# SENSOR.net
KiCad netlist of a schematic drawn in Altium Designer
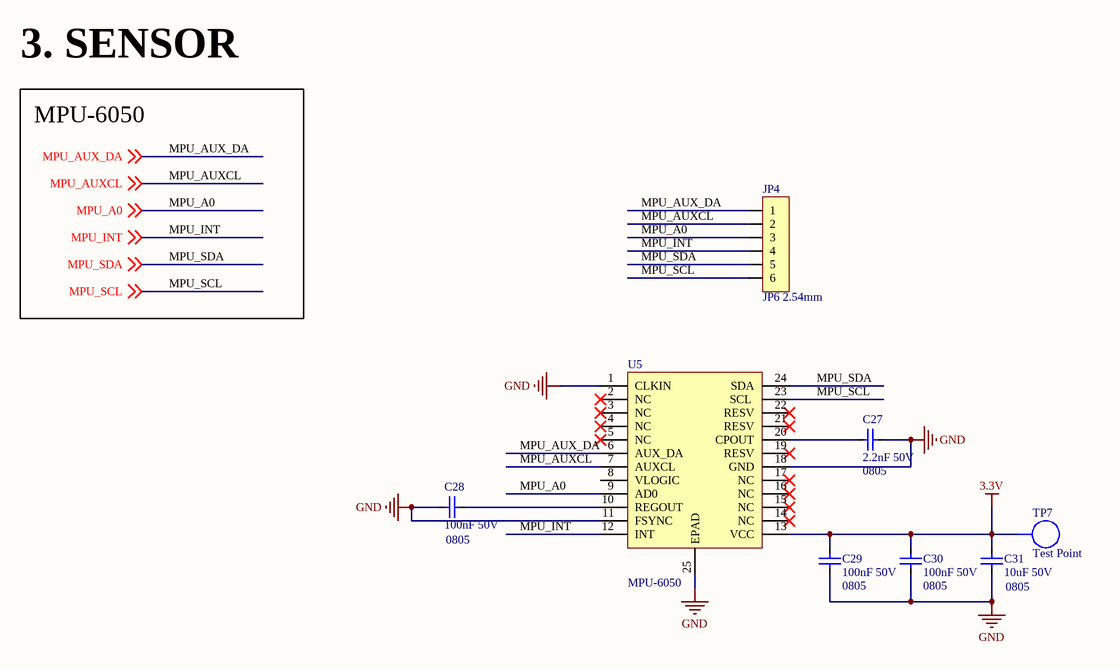
[diagram p0: SENSOR.SchDoc]

(export (version "E")
  (design (tool "Eeschema 10.0.6"))
  (components
    (comp (ref "C27")
      (value "2.2nF 50V")
      (footprint "CAP_SMD_0805_NEW")
      (description "2200 pF ±1% 50V Ceramic Capacitor C0G, NP0 0805 (2012 Metric)")
      (fields
        (field (name "MANUFACTURER") "YAGEO")
        (field (name "MANUFACTURE PART NUMBER") "CC0805FKNPO9BN222")
        (field (name "SIZE") "0805")
      )
      (libsource (lib "Capacitors") (part "C0805_MLCC_2.2nF_50V"))
    )
    (comp (ref "C28")
      (value "100nF 50V")
      (footprint "CAP_SMD_0805_NEW")
      (description "0.1 µF ±10% 50V Ceramic Capacitor X7R 0805 (2012 Metric)")
      (fields
        (field (name "MANUFACTURER") "YAGEO")
        (field (name "MANUFACTURE PART NUMBER") "CC0805KRX7R9BB104")
        (field (name "SIZE") "0805")
      )
      (libsource (lib "Capacitors") (part "C0805_MLCC_100nF_50V"))
    )
    (comp (ref "C29")
      (value "100nF 50V")
      (footprint "CAP_SMD_0805_NEW")
      (description "0.1 µF ±10% 50V Ceramic Capacitor X7R 0805 (2012 Metric)")
      (fields
        (field (name "MANUFACTURER") "YAGEO")
        (field (name "MANUFACTURE PART NUMBER") "CC0805KRX7R9BB104")
        (field (name "SIZE") "0805")
      )
      (libsource (lib "Capacitors") (part "C0805_MLCC_100nF_50V"))
    )
    (comp (ref "C30")
      (value "100nF 50V")
      (footprint "CAP_SMD_0805_NEW")
      (description "0.1 µF ±10% 50V Ceramic Capacitor X7R 0805 (2012 Metric)")
      (fields
        (field (name "MANUFACTURER") "YAGEO")
        (field (name "MANUFACTURE PART NUMBER") "CC0805KRX7R9BB104")
        (field (name "SIZE") "0805")
      )
      (libsource (lib "Capacitors") (part "C0805_MLCC_100nF_50V"))
    )
    (comp (ref "C31")
      (value "10uF 50V")
      (footprint "CAP_SMD_0805_NEW")
      (description "10 µF ±20% 50V Ceramic Capacitor X5R 0805 (2012 Metric)")
      (fields
        (field (name "MANUFACTURER") "Murata Electronics")
        (field (name "MANUFACTURE PART NUMBER") "GRM21BR61H106ME43L")
        (field (name "SIZE") "0805")
      )
      (libsource (lib "Capacitors") (part "C0805_MLCC_10uF_50V"))
    )
    (comp (ref "JP4")
      (value "JP6 2.54mm")
      (footprint "JP6_M")
      (description "Connector Header Through Hole 6 position 0.100\" (2.54mm)")
      (fields
        (field (name "MANUFACTURER") "Würth Elektronik")
        (field (name "MANUFACTURE PART NUMBER") "61300611121")
      )
      (libsource (lib "Connectors") (part "JP6M"))
    )
    (comp (ref "TP7")
      (value "Test Point")
      (footprint "TEST_POINT")
      (libsource (lib "Connectors") (part "TEST_POINT"))
    )
    (comp (ref "U5")
      (value "MPU-6050")
      (footprint "QFN_24")
      (description "Accelerometer, Gyroscope, 6 Axis Sensor I2C Output")
      (fields (field (name "MANUFACTURER") "TDK InvenSense"))
      (libsource (lib "ICs") (part "MPU-6050"))
    )
  )
  (nets
    (net (code "1") (name "3.3V") (class "Default")
      (node (ref "C29") (pin "1") (pinfunction "1_1") (pintype "passive"))
      (node (ref "C30") (pin "1") (pinfunction "1_1") (pintype "passive"))
      (node (ref "C31") (pin "2") (pinfunction "2_2") (pintype "passive"))
      (node (ref "TP7") (pin "1") (pinfunction "1_1") (pintype "passive"))
      (node (ref "U5") (pin "13") (pinfunction "VCC_13") (pintype "passive"))
    )
    (net (code "2") (name "GND") (class "Default")
      (node (ref "C27") (pin "1") (pinfunction "1_1") (pintype "passive"))
      (node (ref "C28") (pin "2") (pinfunction "2_2") (pintype "passive"))
      (node (ref "C29") (pin "2") (pinfunction "2_2") (pintype "passive"))
      (node (ref "C30") (pin "2") (pinfunction "2_2") (pintype "passive"))
      (node (ref "C31") (pin "1") (pinfunction "1_1") (pintype "passive"))
      (node (ref "U5") (pin "1") (pinfunction "CLKIN_1") (pintype "passive"))
      (node (ref "U5") (pin "11") (pinfunction "FSYNC_11") (pintype "passive"))
      (node (ref "U5") (pin "18") (pinfunction "GND_18") (pintype "passive"))
      (node (ref "U5") (pin "25") (pinfunction "EPAD_25") (pintype "passive"))
    )
    (net (code "3") (name "MPU_A0") (class "Default")
      (node (ref "JP4") (pin "3") (pinfunction "3_3") (pintype "passive"))
      (node (ref "U5") (pin "9") (pinfunction "AD0_9") (pintype "passive"))
    )
    (net (code "4") (name "MPU_AUXCL") (class "Default")
      (node (ref "JP4") (pin "2") (pinfunction "2_2") (pintype "passive"))
      (node (ref "U5") (pin "7") (pinfunction "AUXCL_7") (pintype "passive"))
    )
    (net (code "5") (name "MPU_AUX_DA") (class "Default")
      (node (ref "JP4") (pin "1") (pinfunction "1_1") (pintype "passive"))
      (node (ref "U5") (pin "6") (pinfunction "AUX_DA_6") (pintype "passive"))
    )
    (net (code "6") (name "MPU_INT") (class "Default")
      (node (ref "JP4") (pin "4") (pinfunction "4_4") (pintype "passive"))
      (node (ref "U5") (pin "12") (pinfunction "INT_12") (pintype "passive"))
    )
    (net (code "7") (name "MPU_SCL") (class "Default")
      (node (ref "JP4") (pin "6") (pinfunction "6_6") (pintype "passive"))
      (node (ref "U5") (pin "23") (pinfunction "SCL_23") (pintype "passive"))
    )
    (net (code "8") (name "MPU_SDA") (class "Default")
      (node (ref "JP4") (pin "5") (pinfunction "5_5") (pintype "passive"))
      (node (ref "U5") (pin "24") (pinfunction "SDA_24") (pintype "passive"))
    )
    (net (code "9") (name "Net-(U5-CPOUT)") (class "Default")
      (node (ref "C27") (pin "2") (pinfunction "2_2") (pintype "passive"))
      (node (ref "U5") (pin "20") (pinfunction "CPOUT_20") (pintype "passive"))
    )
    (net (code "10") (name "Net-(U5-REGOUT)") (class "Default")
      (node (ref "C28") (pin "1") (pinfunction "1_1") (pintype "passive"))
      (node (ref "U5") (pin "10") (pinfunction "REGOUT_10") (pintype "passive"))
    )
    (net (code "11") (name "unconnected-(U5-NC-Pad2)") (class "Default")
      (node (ref "U5") (pin "2") (pinfunction "NC_2") (pintype "passive+no_connect"))
    )
    (net (code "12") (name "unconnected-(U5-NC-Pad3)") (class "Default")
      (node (ref "U5") (pin "3") (pinfunction "NC_3") (pintype "passive+no_connect"))
    )
    (net (code "13") (name "unconnected-(U5-NC-Pad4)") (class "Default")
      (node (ref "U5") (pin "4") (pinfunction "NC_4") (pintype "passive+no_connect"))
    )
    (net (code "14") (name "unconnected-(U5-NC-Pad5)") (class "Default")
      (node (ref "U5") (pin "5") (pinfunction "NC_5") (pintype "passive+no_connect"))
    )
    (net (code "15") (name "unconnected-(U5-NC-Pad14)") (class "Default")
      (node (ref "U5") (pin "14") (pinfunction "NC_14") (pintype "passive+no_connect"))
    )
    (net (code "16") (name "unconnected-(U5-NC-Pad15)") (class "Default")
      (node (ref "U5") (pin "15") (pinfunction "NC_15") (pintype "passive+no_connect"))
    )
    (net (code "17") (name "unconnected-(U5-NC-Pad16)") (class "Default")
      (node (ref "U5") (pin "16") (pinfunction "NC_16") (pintype "passive+no_connect"))
    )
    (net (code "18") (name "unconnected-(U5-NC-Pad17)") (class "Default")
      (node (ref "U5") (pin "17") (pinfunction "NC_17") (pintype "passive+no_connect"))
    )
    (net (code "19") (name "unconnected-(U5-RESV-Pad19)") (class "Default")
      (node (ref "U5") (pin "19") (pinfunction "RESV_19") (pintype "passive+no_connect"))
    )
    (net (code "20") (name "unconnected-(U5-RESV-Pad21)") (class "Default")
      (node (ref "U5") (pin "21") (pinfunction "RESV_21") (pintype "passive+no_connect"))
    )
    (net (code "21") (name "unconnected-(U5-RESV-Pad22)") (class "Default")
      (node (ref "U5") (pin "22") (pinfunction "RESV_22") (pintype "passive+no_connect"))
    )
    (net (code "22") (name "unconnected-(U5-VLOGIC-Pad8)") (class "Default")
      (node (ref "U5") (pin "8") (pinfunction "VLOGIC_8") (pintype "passive"))
    )
  )
)
